# HC-SR04.net
KiCad netlist of a schematic drawn in Altium Designer
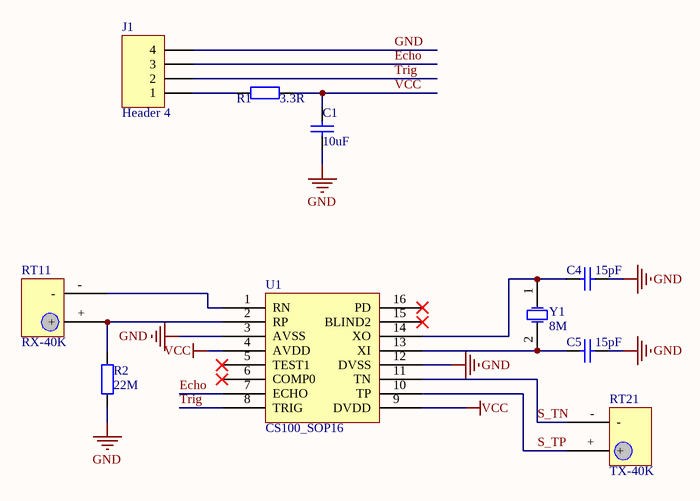
[diagram p0: HC-SR04.SchDoc]

(export (version "E")
  (design (tool "Eeschema 10.0.6"))
  (components
    (comp (ref "C1")
      (value "10uF")
      (footprint "2012[0805]")
      (description "Capacitor")
      (fields (field (name "Comment") "Cap") (field (name "PUBLISHER") "Altium Limited"))
      (libsource (lib "Miscellaneous Devices") (part "Cap"))
    )
    (comp (ref "C4")
      (value "15pF")
      (footprint "1608[0603]")
      (description "Capacitor")
      (fields (field (name "Comment") "Cap") (field (name "PUBLISHER") "Altium Limited"))
      (libsource (lib "Miscellaneous Devices") (part "Cap"))
    )
    (comp (ref "C5")
      (value "15pF")
      (footprint "1608[0603]")
      (description "Capacitor")
      (fields (field (name "Comment") "Cap") (field (name "PUBLISHER") "Altium Limited"))
      (libsource (lib "Miscellaneous Devices") (part "Cap"))
    )
    (comp (ref "J1")
      (value "Header 4")
      (footprint "DIP4-2PCB")
      (description "Header, 4-Pin")
      (fields (field (name "PUBLISHER") "Altium Limited"))
      (libsource (lib "Miscellaneous Connectors") (part "Header 4"))
    )
    (comp (ref "R1")
      (value "3.3R")
      (footprint "1608[0603]")
      (description "Resistor")
      (fields (field (name "Comment") "Res2") (field (name "PUBLISHER") "Altium Limited"))
      (libsource (lib "Miscellaneous Devices") (part "Res2"))
    )
    (comp (ref "R2")
      (value "22M")
      (footprint "1608[0603]")
      (description "Resistor")
      (fields (field (name "Comment") "Res2") (field (name "PUBLISHER") "Altium Limited"))
      (libsource (lib "") (part "Res2_1"))
    )
    (comp (ref "RT11") (value "RX-40K") (footprint "US-16mm") (libsource (lib "USLib") (part "TC40K")))
    (comp (ref "RT21") (value "TX-40K") (footprint "US-16mm") (libsource (lib "") (part "TC40K_1")))
    (comp (ref "U1")
      (value "CS100_SOP16")
      (footprint "SOIC16")
      (libsource (lib "USLib") (part "CS100_SOP16"))
    )
    (comp (ref "Y1")
      (value "8M")
      (footprint "XTAL")
      (description "Crystal Oscillator")
      (fields (field (name "PUBLISHER") "Altium Limited"))
      (libsource (lib "Miscellaneous Devices") (part "XTAL"))
    )
  )
  (nets
    (net (code "1") (name "/Echo") (class "Default")
      (node (ref "J1") (pin "3") (pinfunction "3_3") (pintype "passive"))
      (node (ref "U1") (pin "7") (pinfunction "ECHO_7") (pintype "passive"))
    )
    (net (code "2") (name "/S_TN") (class "Default")
      (node (ref "RT21") (pin "-") (pinfunction "-_-") (pintype "passive"))
      (node (ref "U1") (pin "11") (pinfunction "TN_11") (pintype "passive"))
    )
    (net (code "3") (name "/S_TP") (class "Default")
      (node (ref "RT21") (pin "+") (pinfunction "+_+") (pintype "passive"))
      (node (ref "U1") (pin "10") (pinfunction "TP_10") (pintype "passive"))
    )
    (net (code "4") (name "/Trig") (class "Default")
      (node (ref "J1") (pin "2") (pinfunction "2_2") (pintype "passive"))
      (node (ref "U1") (pin "8") (pinfunction "TRIG_8") (pintype "passive"))
    )
    (net (code "5") (name "GND") (class "Default")
      (node (ref "C1") (pin "1") (pinfunction "1_1") (pintype "passive"))
      (node (ref "C4") (pin "2") (pinfunction "2_2") (pintype "passive"))
      (node (ref "C5") (pin "2") (pinfunction "2_2") (pintype "passive"))
      (node (ref "J1") (pin "4") (pinfunction "4_4") (pintype "passive"))
      (node (ref "R2") (pin "1") (pinfunction "1_1") (pintype "passive"))
      (node (ref "U1") (pin "12") (pinfunction "DVSS_12") (pintype "passive"))
      (node (ref "U1") (pin "3") (pinfunction "AVSS_3") (pintype "passive"))
    )
    (net (code "6") (name "Net-(J1-Pad1)") (class "Default")
      (node (ref "J1") (pin "1") (pinfunction "1_1") (pintype "passive"))
      (node (ref "R1") (pin "1") (pinfunction "1_1") (pintype "passive"))
    )
    (net (code "7") (name "Net-(U1-RN)") (class "Default")
      (node (ref "RT11") (pin "-") (pinfunction "-_-") (pintype "passive"))
      (node (ref "U1") (pin "1") (pinfunction "RN_1") (pintype "passive"))
    )
    (net (code "8") (name "Net-(U1-RP)") (class "Default")
      (node (ref "R2") (pin "2") (pinfunction "2_2") (pintype "passive"))
      (node (ref "RT11") (pin "+") (pinfunction "+_+") (pintype "passive"))
      (node (ref "U1") (pin "2") (pinfunction "RP_2") (pintype "passive"))
    )
    (net (code "9") (name "Net-(U1-XI)") (class "Default")
      (node (ref "C5") (pin "1") (pinfunction "1_1") (pintype "passive"))
      (node (ref "U1") (pin "13") (pinfunction "XI_13") (pintype "passive"))
      (node (ref "Y1") (pin "2") (pinfunction "OSC2_2") (pintype "passive"))
    )
    (net (code "10") (name "Net-(U1-XO)") (class "Default")
      (node (ref "C4") (pin "1") (pinfunction "1_1") (pintype "passive"))
      (node (ref "U1") (pin "14") (pinfunction "XO_14") (pintype "passive"))
      (node (ref "Y1") (pin "1") (pinfunction "OSC1_1") (pintype "passive"))
    )
    (net (code "11") (name "VCC") (class "Default")
      (node (ref "C1") (pin "2") (pinfunction "2_2") (pintype "passive"))
      (node (ref "R1") (pin "2") (pinfunction "2_2") (pintype "passive"))
      (node (ref "U1") (pin "4") (pinfunction "AVDD_4") (pintype "passive"))
      (node (ref "U1") (pin "9") (pinfunction "DVDD_9") (pintype "passive"))
    )
    (net (code "12") (name "unconnected-(U1-BLIND2-Pad15)") (class "Default")
      (node (ref "U1") (pin "15") (pinfunction "BLIND2_15") (pintype "passive+no_connect"))
    )
    (net (code "13") (name "unconnected-(U1-COMP0-Pad6)") (class "Default")
      (node (ref "U1") (pin "6") (pinfunction "COMP0_6") (pintype "passive+no_connect"))
    )
    (net (code "14") (name "unconnected-(U1-PD-Pad16)") (class "Default")
      (node (ref "U1") (pin "16") (pinfunction "PD_16") (pintype "passive+no_connect"))
    )
    (net (code "15") (name "unconnected-(U1-TEST1-Pad5)") (class "Default")
      (node (ref "U1") (pin "5") (pinfunction "TEST1_5") (pintype "passive+no_connect"))
    )
  )
)
